# 2_mb_conn.net
KiCad netlist of a schematic drawn in Altium Designer
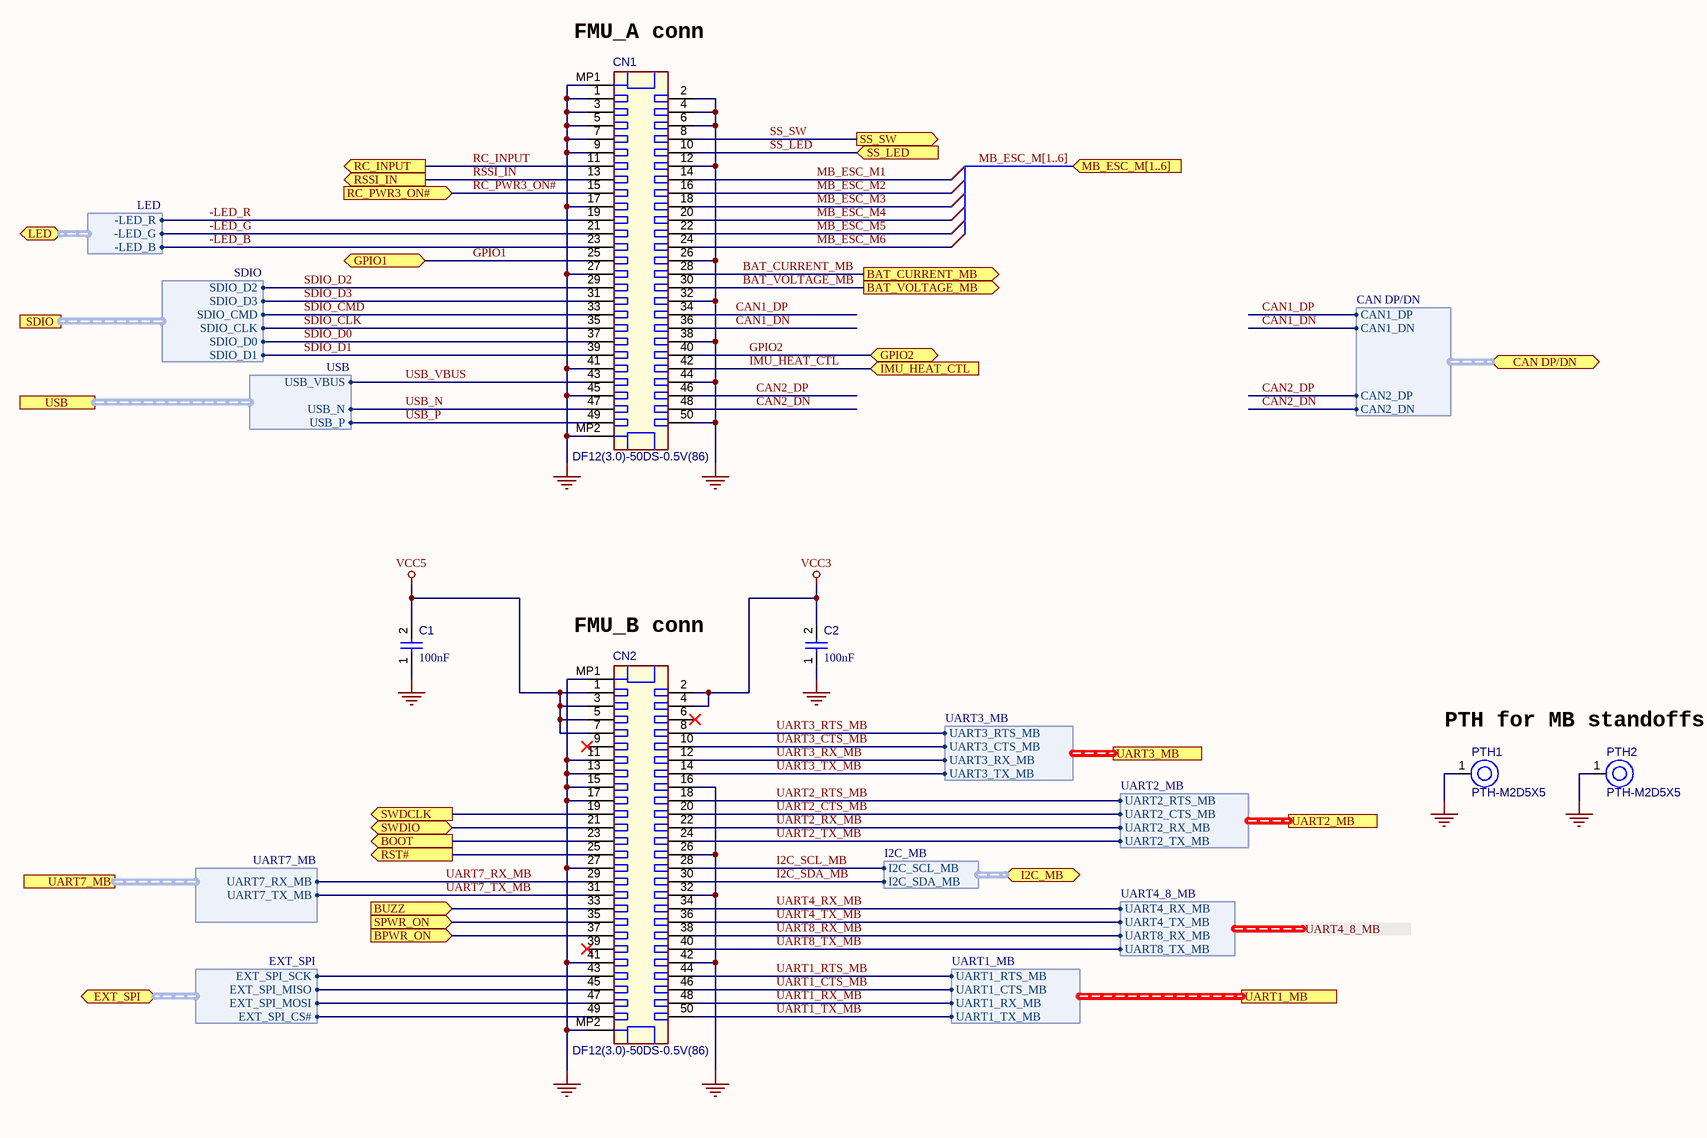
[diagram p0:  2_mb_conn.SchDoc]

(export (version "E")
  (design (tool "Eeschema 10.0.6"))
  (components
    (comp (ref "C1")
      (value "100nF")
      (footprint "CAPC0402(1005)60_L")
      (description "Chip Capacitor, 100nF +/-20%, 10V, 0402, Thickness 0.6 mm")
      (fields (field (name "TOLERANCE") "20%") (field (name "Comment") "Capacitor 100nF +/-20% 10V 0402"))
      (libsource (lib "MHH -  Altium Advanced Course A365 01") (part "CAP-NP-2"))
    )
    (comp (ref "C2")
      (value "100nF")
      (footprint "CAPC0402(1005)60_L")
      (description "Chip Capacitor, 100nF +/-20%, 10V, 0402, Thickness 0.6 mm")
      (fields (field (name "TOLERANCE") "20%") (field (name "Comment") "Capacitor 100nF +/-20% 10V 0402"))
      (libsource (lib "MHH -  Altium Advanced Course A365 01") (part "CAP-NP-2"))
    )
    (comp (ref "CN1")
      (value "DF12(3.0)-50DS-0.5V(86)")
      (footprint "HIRO-DF12(3.0)-50DS-0.5V_V")
      (description "Receptacle Connector, 50 V, 0.3 A, -45 to 125 degC, RoHS, Tape and Reel")
      (libsource (lib "MHH -  Altium Advanced Course A365 01") (part "CMP-00111-4"))
    )
    (comp (ref "CN2")
      (value "DF12(3.0)-50DS-0.5V(86)")
      (footprint "HIRO-DF12(3.0)-50DS-0.5V_V")
      (description "Receptacle Connector, 50 V, 0.3 A, -45 to 125 degC, RoHS, Tape and Reel")
      (libsource (lib "MHH -  Altium Advanced Course A365 01") (part "CMP-00111-4"))
    )
    (comp (ref "PTH1")
      (value "PTH-M2D5X5")
      (footprint "PTH-M2D5X5")
      (description "M2 PTH (2.5mm), 5mm pad")
      (libsource (lib "MHH -  Altium Advanced Course A365 01") (part "CMP-00028-00000-1"))
    )
    (comp (ref "PTH2")
      (value "PTH-M2D5X5")
      (footprint "PTH-M2D5X5")
      (description "M2 PTH (2.5mm), 5mm pad")
      (libsource (lib "MHH -  Altium Advanced Course A365 01") (part "CMP-00028-00000-1"))
    )
  )
  (nets
    (net (code "13") (name "/-LED_B") (class "Default")
      (node (ref "CN1") (pin "23") (pinfunction "23_23") (pintype "passive"))
    )
    (net (code "14") (name "/-LED_G") (class "Default")
      (node (ref "CN1") (pin "21") (pinfunction "21_21") (pintype "passive"))
    )
    (net (code "15") (name "/-LED_R") (class "Default")
      (node (ref "CN1") (pin "19") (pinfunction "19_19") (pintype "passive"))
    )
    (net (code "16") (name "/BAT_CURRENT_MB") (class "Default")
      (node (ref "CN1") (pin "28") (pinfunction "28_28") (pintype "passive"))
    )
    (net (code "17") (name "/BAT_VOLTAGE_MB") (class "Default")
      (node (ref "CN1") (pin "30") (pinfunction "30_30") (pintype "passive"))
    )
    (net (code "18") (name "/BOOT") (class "Default")
      (node (ref "CN2") (pin "23") (pinfunction "23_23") (pintype "passive"))
    )
    (net (code "19") (name "/BPWR_ON") (class "Default")
      (node (ref "CN2") (pin "37") (pinfunction "37_37") (pintype "passive"))
    )
    (net (code "20") (name "/BUZZ") (class "Default")
      (node (ref "CN2") (pin "33") (pinfunction "33_33") (pintype "passive"))
    )
    (net (code "21") (name "/CAN1_DN") (class "Default")
      (node (ref "CN1") (pin "36") (pinfunction "36_36") (pintype "passive"))
    )
    (net (code "22") (name "/CAN1_DP") (class "Default")
      (node (ref "CN1") (pin "34") (pinfunction "34_34") (pintype "passive"))
    )
    (net (code "23") (name "/CAN2_DN") (class "Default")
      (node (ref "CN1") (pin "48") (pinfunction "48_48") (pintype "passive"))
    )
    (net (code "24") (name "/CAN2_DP") (class "Default")
      (node (ref "CN1") (pin "46") (pinfunction "46_46") (pintype "passive"))
    )
    (net (code "25") (name "/EXT_SPI_CS#") (class "Default")
      (node (ref "CN2") (pin "49") (pinfunction "49_49") (pintype "passive"))
    )
    (net (code "26") (name "/EXT_SPI_MISO") (class "Default")
      (node (ref "CN2") (pin "45") (pinfunction "45_45") (pintype "passive"))
    )
    (net (code "27") (name "/EXT_SPI_MOSI") (class "Default")
      (node (ref "CN2") (pin "47") (pinfunction "47_47") (pintype "passive"))
    )
    (net (code "28") (name "/EXT_SPI_SCK") (class "Default")
      (node (ref "CN2") (pin "43") (pinfunction "43_43") (pintype "passive"))
    )
    (net (code "29") (name "/GPIO1") (class "Default")
      (node (ref "CN1") (pin "25") (pinfunction "25_25") (pintype "passive"))
    )
    (net (code "30") (name "/GPIO2") (class "Default")
      (node (ref "CN1") (pin "40") (pinfunction "40_40") (pintype "passive"))
    )
    (net (code "31") (name "/I2C_SCL_MB") (class "Default")
      (node (ref "CN2") (pin "28") (pinfunction "28_28") (pintype "passive"))
    )
    (net (code "32") (name "/I2C_SDA_MB") (class "Default")
      (node (ref "CN2") (pin "30") (pinfunction "30_30") (pintype "passive"))
    )
    (net (code "33") (name "/IMU_HEAT_CTL") (class "Default")
      (node (ref "CN1") (pin "42") (pinfunction "42_42") (pintype "passive"))
    )
    (net (code "34") (name "/MB_ESC_M1") (class "Default")
      (node (ref "CN1") (pin "14") (pinfunction "14_14") (pintype "passive"))
    )
    (net (code "35") (name "/MB_ESC_M2") (class "Default")
      (node (ref "CN1") (pin "16") (pinfunction "16_16") (pintype "passive"))
    )
    (net (code "36") (name "/MB_ESC_M3") (class "Default")
      (node (ref "CN1") (pin "18") (pinfunction "18_18") (pintype "passive"))
    )
    (net (code "37") (name "/MB_ESC_M4") (class "Default")
      (node (ref "CN1") (pin "20") (pinfunction "20_20") (pintype "passive"))
    )
    (net (code "38") (name "/MB_ESC_M5") (class "Default")
      (node (ref "CN1") (pin "22") (pinfunction "22_22") (pintype "passive"))
    )
    (net (code "39") (name "/MB_ESC_M6") (class "Default")
      (node (ref "CN1") (pin "24") (pinfunction "24_24") (pintype "passive"))
    )
    (net (code "41") (name "/RC_INPUT") (class "Default")
      (node (ref "CN1") (pin "11") (pinfunction "11_11") (pintype "passive"))
    )
    (net (code "42") (name "/RC_PWR3_ON#") (class "Default")
      (node (ref "CN1") (pin "15") (pinfunction "15_15") (pintype "passive"))
    )
    (net (code "43") (name "/RSSI_IN") (class "Default")
      (node (ref "CN1") (pin "13") (pinfunction "13_13") (pintype "passive"))
    )
    (net (code "44") (name "/RST#") (class "Default")
      (node (ref "CN2") (pin "25") (pinfunction "25_25") (pintype "passive"))
    )
    (net (code "45") (name "/SDIO_CLK") (class "Default")
      (node (ref "CN1") (pin "35") (pinfunction "35_35") (pintype "passive"))
    )
    (net (code "46") (name "/SDIO_CMD") (class "Default")
      (node (ref "CN1") (pin "33") (pinfunction "33_33") (pintype "passive"))
    )
    (net (code "47") (name "/SDIO_D0") (class "Default")
      (node (ref "CN1") (pin "37") (pinfunction "37_37") (pintype "passive"))
    )
    (net (code "48") (name "/SDIO_D1") (class "Default")
      (node (ref "CN1") (pin "39") (pinfunction "39_39") (pintype "passive"))
    )
    (net (code "49") (name "/SDIO_D2") (class "Default")
      (node (ref "CN1") (pin "29") (pinfunction "29_29") (pintype "passive"))
    )
    (net (code "50") (name "/SDIO_D3") (class "Default")
      (node (ref "CN1") (pin "31") (pinfunction "31_31") (pintype "passive"))
    )
    (net (code "51") (name "/SPWR_ON") (class "Default")
      (node (ref "CN2") (pin "35") (pinfunction "35_35") (pintype "passive"))
    )
    (net (code "52") (name "/SS_LED") (class "Default")
      (node (ref "CN1") (pin "10") (pinfunction "10_10") (pintype "passive"))
    )
    (net (code "53") (name "/SS_SW") (class "Default")
      (node (ref "CN1") (pin "8") (pinfunction "8_8") (pintype "passive"))
    )
    (net (code "54") (name "/SWDCLK") (class "Default")
      (node (ref "CN2") (pin "19") (pinfunction "19_19") (pintype "passive"))
    )
    (net (code "55") (name "/SWDIO") (class "Default")
      (node (ref "CN2") (pin "21") (pinfunction "21_21") (pintype "passive"))
    )
    (net (code "56") (name "/UART1_CTS_MB") (class "Default")
      (node (ref "CN2") (pin "46") (pinfunction "46_46") (pintype "passive"))
    )
    (net (code "57") (name "/UART1_RTS_MB") (class "Default")
      (node (ref "CN2") (pin "44") (pinfunction "44_44") (pintype "passive"))
    )
    (net (code "58") (name "/UART1_RX_MB") (class "Default")
      (node (ref "CN2") (pin "48") (pinfunction "48_48") (pintype "passive"))
    )
    (net (code "59") (name "/UART1_TX_MB") (class "Default")
      (node (ref "CN2") (pin "50") (pinfunction "50_50") (pintype "passive"))
    )
    (net (code "60") (name "/UART2_CTS_MB") (class "Default")
      (node (ref "CN2") (pin "20") (pinfunction "20_20") (pintype "passive"))
    )
    (net (code "61") (name "/UART2_RTS_MB") (class "Default")
      (node (ref "CN2") (pin "18") (pinfunction "18_18") (pintype "passive"))
    )
    (net (code "62") (name "/UART2_RX_MB") (class "Default")
      (node (ref "CN2") (pin "22") (pinfunction "22_22") (pintype "passive"))
    )
    (net (code "63") (name "/UART2_TX_MB") (class "Default")
      (node (ref "CN2") (pin "24") (pinfunction "24_24") (pintype "passive"))
    )
    (net (code "64") (name "/UART3_CTS_MB") (class "Default")
      (node (ref "CN2") (pin "10") (pinfunction "10_10") (pintype "passive"))
    )
    (net (code "65") (name "/UART3_RTS_MB") (class "Default")
      (node (ref "CN2") (pin "8") (pinfunction "8_8") (pintype "passive"))
    )
    (net (code "66") (name "/UART3_RX_MB") (class "Default")
      (node (ref "CN2") (pin "12") (pinfunction "12_12") (pintype "passive"))
    )
    (net (code "67") (name "/UART3_TX_MB") (class "Default")
      (node (ref "CN2") (pin "14") (pinfunction "14_14") (pintype "passive"))
    )
    (net (code "68") (name "/UART4_RX_MB") (class "Default")
      (node (ref "CN2") (pin "34") (pinfunction "34_34") (pintype "passive"))
    )
    (net (code "69") (name "/UART4_TX_MB") (class "Default")
      (node (ref "CN2") (pin "36") (pinfunction "36_36") (pintype "passive"))
    )
    (net (code "70") (name "/UART7_RX_MB") (class "Default")
      (node (ref "CN2") (pin "29") (pinfunction "29_29") (pintype "passive"))
    )
    (net (code "71") (name "/UART7_TX_MB") (class "Default")
      (node (ref "CN2") (pin "31") (pinfunction "31_31") (pintype "passive"))
    )
    (net (code "72") (name "/UART8_RX_MB") (class "Default")
      (node (ref "CN2") (pin "38") (pinfunction "38_38") (pintype "passive"))
    )
    (net (code "73") (name "/UART8_TX_MB") (class "Default")
      (node (ref "CN2") (pin "40") (pinfunction "40_40") (pintype "passive"))
    )
    (net (code "74") (name "/USB_N") (class "Default")
      (node (ref "CN1") (pin "47") (pinfunction "47_47") (pintype "passive"))
    )
    (net (code "75") (name "/USB_P") (class "Default")
      (node (ref "CN1") (pin "49") (pinfunction "49_49") (pintype "passive"))
    )
    (net (code "76") (name "/USB_VBUS") (class "Default")
      (node (ref "CN1") (pin "43") (pinfunction "43_43") (pintype "passive"))
    )
    (net (code "88") (name "GND") (class "Default")
      (node (ref "C1") (pin "1") (pinfunction "1_1") (pintype "passive"))
      (node (ref "C2") (pin "1") (pinfunction "1_1") (pintype "passive"))
      (node (ref "CN1") (pin "1") (pinfunction "1_1") (pintype "passive"))
      (node (ref "CN1") (pin "12") (pinfunction "12_12") (pintype "passive"))
      (node (ref "CN1") (pin "17") (pinfunction "17_17") (pintype "passive"))
      (node (ref "CN1") (pin "2") (pinfunction "2_2") (pintype "passive"))
      (node (ref "CN1") (pin "26") (pinfunction "26_26") (pintype "passive"))
      (node (ref "CN1") (pin "27") (pinfunction "27_27") (pintype "passive"))
      (node (ref "CN1") (pin "3") (pinfunction "3_3") (pintype "passive"))
      (node (ref "CN1") (pin "32") (pinfunction "32_32") (pintype "passive"))
      (node (ref "CN1") (pin "38") (pinfunction "38_38") (pintype "passive"))
      (node (ref "CN1") (pin "4") (pinfunction "4_4") (pintype "passive"))
      (node (ref "CN1") (pin "41") (pinfunction "41_41") (pintype "passive"))
      (node (ref "CN1") (pin "44") (pinfunction "44_44") (pintype "passive"))
      (node (ref "CN1") (pin "45") (pinfunction "45_45") (pintype "passive"))
      (node (ref "CN1") (pin "5") (pinfunction "5_5") (pintype "passive"))
      (node (ref "CN1") (pin "50") (pinfunction "50_50") (pintype "passive"))
      (node (ref "CN1") (pin "6") (pinfunction "6_6") (pintype "passive"))
      (node (ref "CN1") (pin "7") (pinfunction "7_7") (pintype "passive"))
      (node (ref "CN1") (pin "9") (pinfunction "9_9") (pintype "passive"))
      (node (ref "CN1") (pin "MP1") (pinfunction "MP1_MP1") (pintype "passive"))
      (node (ref "CN1") (pin "MP2") (pinfunction "MP2_MP2") (pintype "passive"))
      (node (ref "CN2") (pin "11") (pinfunction "11_11") (pintype "passive"))
      (node (ref "CN2") (pin "13") (pinfunction "13_13") (pintype "passive"))
      (node (ref "CN2") (pin "15") (pinfunction "15_15") (pintype "passive"))
      (node (ref "CN2") (pin "16") (pinfunction "16_16") (pintype "passive"))
      (node (ref "CN2") (pin "17") (pinfunction "17_17") (pintype "passive"))
      (node (ref "CN2") (pin "26") (pinfunction "26_26") (pintype "passive"))
      (node (ref "CN2") (pin "27") (pinfunction "27_27") (pintype "passive"))
      (node (ref "CN2") (pin "32") (pinfunction "32_32") (pintype "passive"))
      (node (ref "CN2") (pin "41") (pinfunction "41_41") (pintype "passive"))
      (node (ref "CN2") (pin "42") (pinfunction "42_42") (pintype "passive"))
      (node (ref "CN2") (pin "MP1") (pinfunction "MP1_MP1") (pintype "passive"))
      (node (ref "CN2") (pin "MP2") (pinfunction "MP2_MP2") (pintype "passive"))
      (node (ref "PTH1") (pin "1") (pinfunction "H1_1") (pintype "passive"))
      (node (ref "PTH2") (pin "1") (pinfunction "H1_1") (pintype "passive"))
    )
    (net (code "89") (name "VCC3") (class "Default")
      (node (ref "C2") (pin "2") (pinfunction "2_2") (pintype "passive"))
      (node (ref "CN2") (pin "2") (pinfunction "2_2") (pintype "passive"))
      (node (ref "CN2") (pin "4") (pinfunction "4_4") (pintype "passive"))
    )
    (net (code "90") (name "VCC5") (class "Default")
      (node (ref "C1") (pin "2") (pinfunction "2_2") (pintype "passive"))
      (node (ref "CN2") (pin "1") (pinfunction "1_1") (pintype "passive"))
      (node (ref "CN2") (pin "3") (pinfunction "3_3") (pintype "passive"))
      (node (ref "CN2") (pin "5") (pinfunction "5_5") (pintype "passive"))
      (node (ref "CN2") (pin "7") (pinfunction "7_7") (pintype "passive"))
    )
    (net (code "91") (name "unconnected-(CN2-Pad6)") (class "Default")
      (node (ref "CN2") (pin "6") (pinfunction "6_6") (pintype "passive+no_connect"))
    )
    (net (code "92") (name "unconnected-(CN2-Pad9)") (class "Default")
      (node (ref "CN2") (pin "9") (pinfunction "9_9") (pintype "passive+no_connect"))
    )
    (net (code "93") (name "unconnected-(CN2-Pad39)") (class "Default")
      (node (ref "CN2") (pin "39") (pinfunction "39_39") (pintype "passive+no_connect"))
    )
  )
)
